# SH7_-_GPIO_Expander.net
KiCad netlist of a schematic drawn in Altium Designer
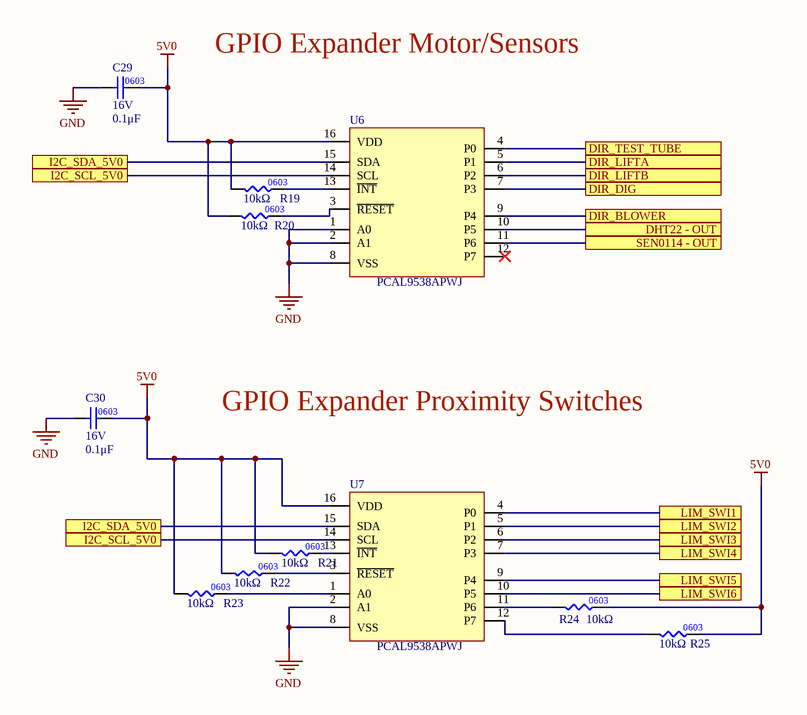
[diagram p0: SH7 - GPIO Expander.SchDoc]

(export (version "E")
  (design (tool "Eeschema 10.0.6"))
  (components
    (comp (ref "C29")
      (value "0.1μF")
      (footprint "CAP0603")
      (description "CAP CER 0.1UF 16V X7R 0603")
      (fields (field (name "VOLTAGE RATING") "16V") (field (name "Comment") "CAP_0.1uF_16V_0603"))
      (libsource (lib "UWRT_Schematic_Library_2020") (part "CAP_0.1uF_16V_0603"))
    )
    (comp (ref "C30")
      (value "0.1μF")
      (footprint "CAP0603")
      (description "CAP CER 0.1UF 16V X7R 0603")
      (fields (field (name "VOLTAGE RATING") "16V") (field (name "Comment") "CAP_0.1uF_16V_0603"))
      (libsource (lib "UWRT_Schematic_Library_2020") (part "CAP_0.1uF_16V_0603"))
    )
    (comp (ref "R19")
      (value "10kΩ")
      (footprint "RES0603")
      (description "RES 10K OHM 5% 1/10W 0603")
      (fields (field (name "Comment") "RES_10kΩ_0603_5%"))
      (libsource (lib "UWRT_Schematic_Library_2020") (part "RES_10kΩ_0603_5%"))
    )
    (comp (ref "R20")
      (value "10kΩ")
      (footprint "RES0603")
      (description "RES 10K OHM 5% 1/10W 0603")
      (fields (field (name "Comment") "RES_10kΩ_0603_5%"))
      (libsource (lib "UWRT_Schematic_Library_2020") (part "RES_10kΩ_0603_5%"))
    )
    (comp (ref "R21")
      (value "10kΩ")
      (footprint "RES0603")
      (description "RES 10K OHM 5% 1/10W 0603")
      (fields (field (name "Comment") "RES_10kΩ_0603_5%"))
      (libsource (lib "UWRT_Schematic_Library_2020") (part "RES_10kΩ_0603_5%"))
    )
    (comp (ref "R22")
      (value "10kΩ")
      (footprint "RES0603")
      (description "RES 10K OHM 5% 1/10W 0603")
      (fields (field (name "Comment") "RES_10kΩ_0603_5%"))
      (libsource (lib "UWRT_Schematic_Library_2020") (part "RES_10kΩ_0603_5%"))
    )
    (comp (ref "R23")
      (value "10kΩ")
      (footprint "RES0603")
      (description "RES 10K OHM 5% 1/10W 0603")
      (fields (field (name "Comment") "RES_10kΩ_0603_5%"))
      (libsource (lib "UWRT_Schematic_Library_2020") (part "RES_10kΩ_0603_5%"))
    )
    (comp (ref "R24")
      (value "10kΩ")
      (footprint "RES0603")
      (description "RES 10K OHM 5% 1/10W 0603")
      (fields (field (name "Comment") "RES_10kΩ_0603_5%"))
      (libsource (lib "UWRT_Schematic_Library_2020") (part "RES_10kΩ_0603_5%"))
    )
    (comp (ref "R25")
      (value "10kΩ")
      (footprint "RES0603")
      (description "RES 10K OHM 5% 1/10W 0603")
      (fields (field (name "Comment") "RES_10kΩ_0603_5%"))
      (libsource (lib "UWRT_Schematic_Library_2020") (part "RES_10kΩ_0603_5%"))
    )
    (comp (ref "U6")
      (value "8 Channel I2C GPIO Expander")
      (footprint "TSSOP16")
      (fields (field (name "MANUFACTURER") "NXP USA Inc."))
      (libsource (lib "UWRT_Schematic_Library_2020") (part "IC_GPIO_I2C_EXPANDER 8CH 16TSSOP"))
    )
    (comp (ref "U7")
      (value "8 Channel I2C GPIO Expander")
      (footprint "TSSOP16")
      (fields (field (name "MANUFACTURER") "NXP USA Inc."))
      (libsource (lib "UWRT_Schematic_Library_2020") (part "IC_GPIO_I2C_EXPANDER 8CH 16TSSOP"))
    )
  )
  (nets
    (net (code "1") (name "/DHT22 - OUT") (class "Default")
      (node (ref "U6") (pin "10") (pinfunction "P5_10") (pintype "passive"))
    )
    (net (code "2") (name "/DIR_BLOWER") (class "Default")
      (node (ref "U6") (pin "9") (pinfunction "P4_9") (pintype "passive"))
    )
    (net (code "3") (name "/DIR_DIG") (class "Default")
      (node (ref "U6") (pin "7") (pinfunction "P3_7") (pintype "passive"))
    )
    (net (code "4") (name "/DIR_LIFTA") (class "Default")
      (node (ref "U6") (pin "5") (pinfunction "P1_5") (pintype "passive"))
    )
    (net (code "5") (name "/DIR_LIFTB") (class "Default")
      (node (ref "U6") (pin "6") (pinfunction "P2_6") (pintype "passive"))
    )
    (net (code "6") (name "/DIR_TEST_TUBE") (class "Default")
      (node (ref "U6") (pin "4") (pinfunction "P0_4") (pintype "passive"))
    )
    (net (code "7") (name "/I2C_SCL_5V0") (class "Default")
      (node (ref "U6") (pin "14") (pinfunction "SCL_14") (pintype "passive"))
      (node (ref "U7") (pin "14") (pinfunction "SCL_14") (pintype "passive"))
    )
    (net (code "8") (name "/I2C_SDA_5V0") (class "Default")
      (node (ref "U6") (pin "15") (pinfunction "SDA_15") (pintype "passive"))
      (node (ref "U7") (pin "15") (pinfunction "SDA_15") (pintype "passive"))
    )
    (net (code "9") (name "/LIM_SWI1") (class "Default")
      (node (ref "U7") (pin "4") (pinfunction "P0_4") (pintype "passive"))
    )
    (net (code "10") (name "/LIM_SWI2") (class "Default")
      (node (ref "U7") (pin "5") (pinfunction "P1_5") (pintype "passive"))
    )
    (net (code "11") (name "/LIM_SWI3") (class "Default")
      (node (ref "U7") (pin "6") (pinfunction "P2_6") (pintype "passive"))
    )
    (net (code "12") (name "/LIM_SWI4") (class "Default")
      (node (ref "U7") (pin "7") (pinfunction "P3_7") (pintype "passive"))
    )
    (net (code "13") (name "/LIM_SWI5") (class "Default")
      (node (ref "U7") (pin "9") (pinfunction "P4_9") (pintype "passive"))
    )
    (net (code "14") (name "/LIM_SWI6") (class "Default")
      (node (ref "U7") (pin "10") (pinfunction "P5_10") (pintype "passive"))
    )
    (net (code "15") (name "/SEN0114 - OUT") (class "Default")
      (node (ref "U6") (pin "11") (pinfunction "P6_11") (pintype "passive"))
    )
    (net (code "16") (name "5V0") (class "Default")
      (node (ref "C29") (pin "2") (pinfunction "2_2") (pintype "passive"))
      (node (ref "C30") (pin "2") (pinfunction "2_2") (pintype "passive"))
      (node (ref "R19") (pin "1") (pinfunction "1_1") (pintype "passive"))
      (node (ref "R20") (pin "1") (pinfunction "1_1") (pintype "passive"))
      (node (ref "R21") (pin "1") (pinfunction "1_1") (pintype "passive"))
      (node (ref "R22") (pin "1") (pinfunction "1_1") (pintype "passive"))
      (node (ref "R23") (pin "1") (pinfunction "1_1") (pintype "passive"))
      (node (ref "R24") (pin "2") (pinfunction "2_2") (pintype "passive"))
      (node (ref "R25") (pin "2") (pinfunction "2_2") (pintype "passive"))
      (node (ref "U6") (pin "16") (pinfunction "VDD_16") (pintype "passive"))
      (node (ref "U7") (pin "16") (pinfunction "VDD_16") (pintype "passive"))
    )
    (net (code "17") (name "GND") (class "Default")
      (node (ref "C29") (pin "1") (pinfunction "1_1") (pintype "passive"))
      (node (ref "C30") (pin "1") (pinfunction "1_1") (pintype "passive"))
      (node (ref "U6") (pin "1") (pinfunction "A0_1") (pintype "passive"))
      (node (ref "U6") (pin "2") (pinfunction "A1_2") (pintype "passive"))
      (node (ref "U6") (pin "8") (pinfunction "VSS_8") (pintype "passive"))
      (node (ref "U7") (pin "2") (pinfunction "A1_2") (pintype "passive"))
      (node (ref "U7") (pin "8") (pinfunction "VSS_8") (pintype "passive"))
    )
    (net (code "18") (name "Net-(U6-~{INT})") (class "Default")
      (node (ref "R19") (pin "2") (pinfunction "2_2") (pintype "passive"))
      (node (ref "U6") (pin "13") (pinfunction "~{INT}_13") (pintype "passive"))
    )
    (net (code "19") (name "Net-(U6-~{RESET})") (class "Default")
      (node (ref "R20") (pin "2") (pinfunction "2_2") (pintype "passive"))
      (node (ref "U6") (pin "3") (pinfunction "~{RESET}_3") (pintype "passive"))
    )
    (net (code "20") (name "Net-(U7-A0)") (class "Default")
      (node (ref "R23") (pin "2") (pinfunction "2_2") (pintype "passive"))
      (node (ref "U7") (pin "1") (pinfunction "A0_1") (pintype "passive"))
    )
    (net (code "21") (name "Net-(U7-P6)") (class "Default")
      (node (ref "R24") (pin "1") (pinfunction "1_1") (pintype "passive"))
      (node (ref "U7") (pin "11") (pinfunction "P6_11") (pintype "passive"))
    )
    (net (code "22") (name "Net-(U7-P7)") (class "Default")
      (node (ref "R25") (pin "1") (pinfunction "1_1") (pintype "passive"))
      (node (ref "U7") (pin "12") (pinfunction "P7_12") (pintype "passive"))
    )
    (net (code "23") (name "Net-(U7-~{INT})") (class "Default")
      (node (ref "R21") (pin "2") (pinfunction "2_2") (pintype "passive"))
      (node (ref "U7") (pin "13") (pinfunction "~{INT}_13") (pintype "passive"))
    )
    (net (code "24") (name "Net-(U7-~{RESET})") (class "Default")
      (node (ref "R22") (pin "2") (pinfunction "2_2") (pintype "passive"))
      (node (ref "U7") (pin "3") (pinfunction "~{RESET}_3") (pintype "passive"))
    )
    (net (code "25") (name "unconnected-(U6-P7-Pad12)") (class "Default")
      (node (ref "U6") (pin "12") (pinfunction "P7_12") (pintype "passive+no_connect"))
    )
  )
)
